# LED_board.net
KiCad netlist of a schematic drawn in EAGLE
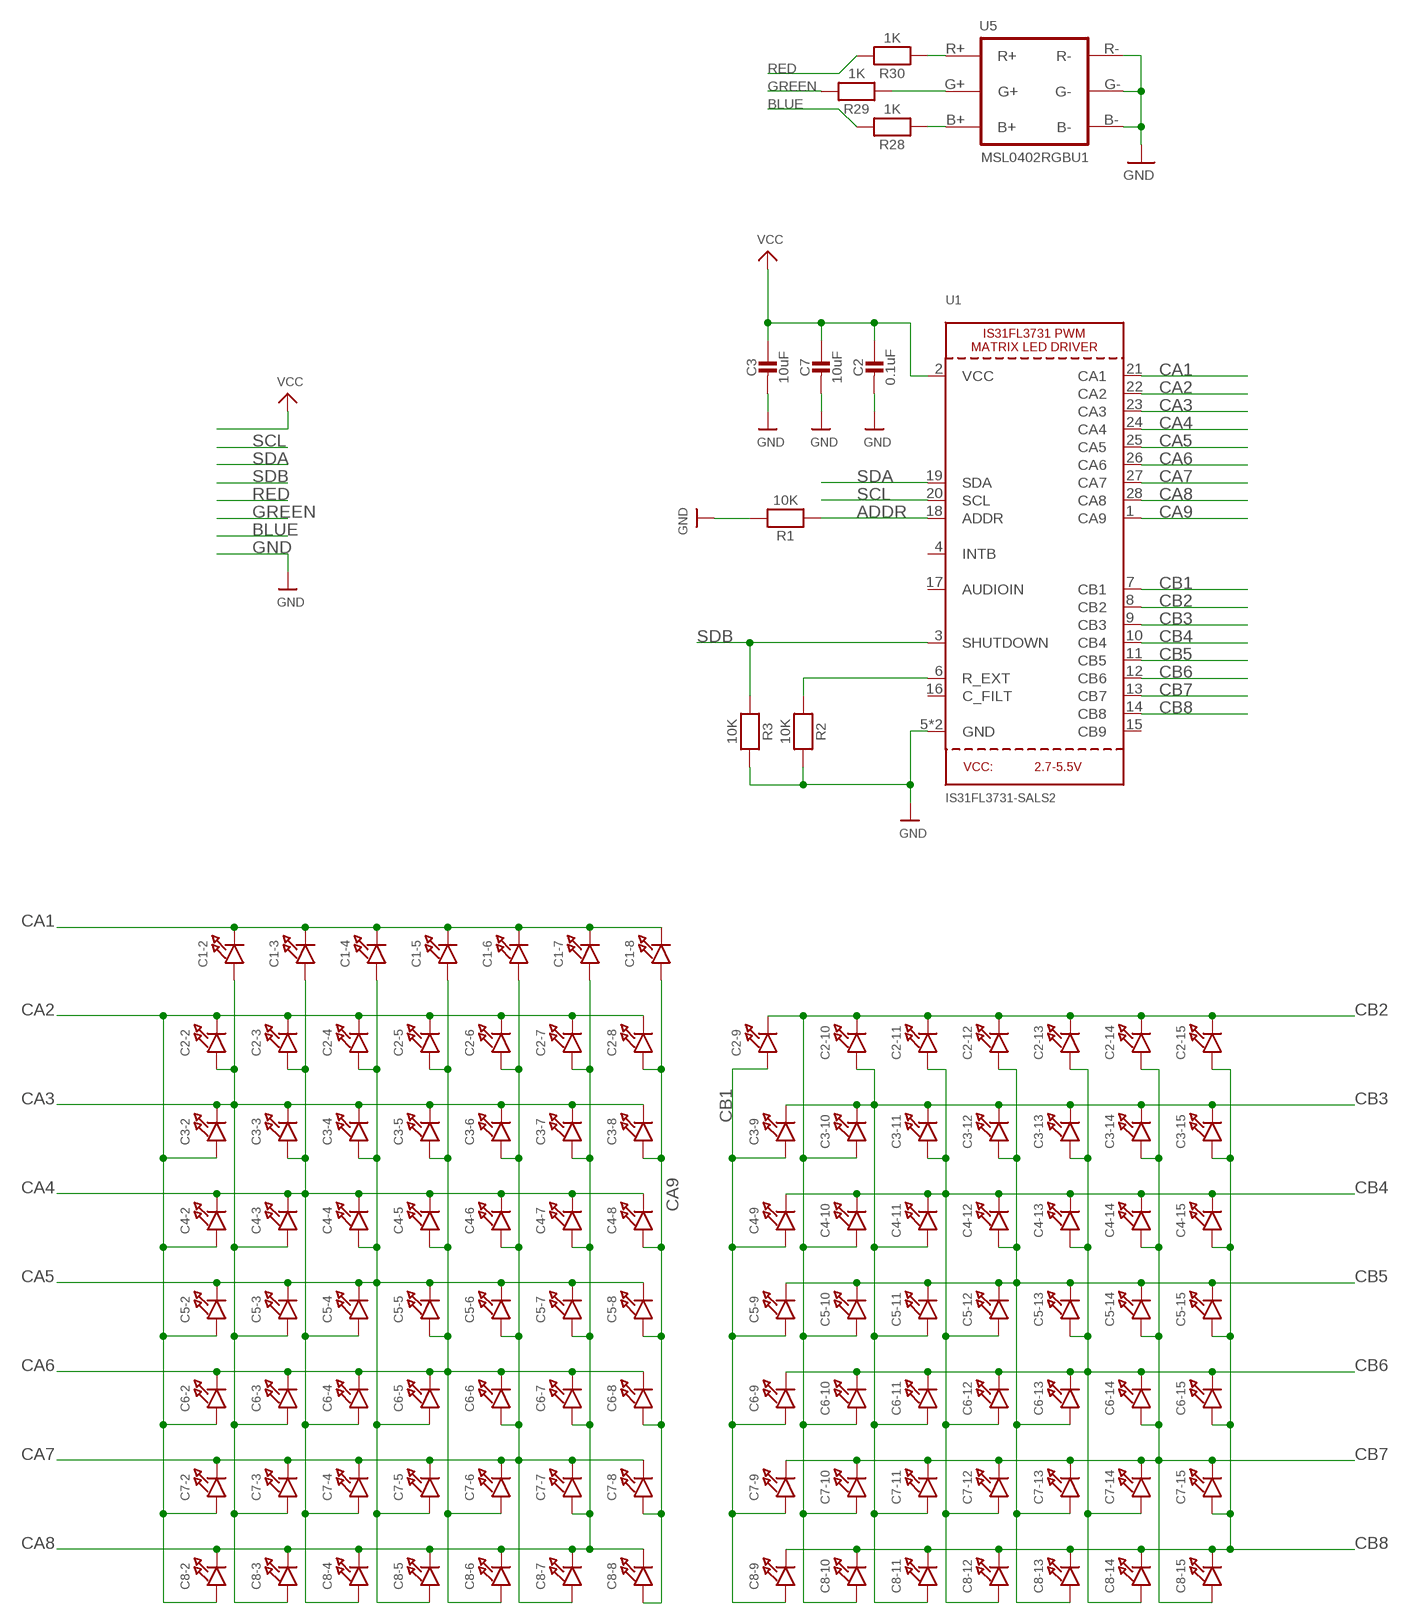
[diagram p0: schematic, sheet 1]

(export (version "E")
  (design (tool "Eeschema 10.0.6"))
  (components
    (comp (ref "C1-2")
      (value "LED0603_NOOUTLINE")
      (footprint "eagle-import:CHIPLED_0603_NOOUTLINE")
      (libsource (lib "eagle-import") (part "LED0603_NOOUTLINE"))
    )
    (comp (ref "C1-3")
      (value "LED0603_NOOUTLINE")
      (footprint "eagle-import:CHIPLED_0603_NOOUTLINE")
      (libsource (lib "eagle-import") (part "LED0603_NOOUTLINE"))
    )
    (comp (ref "C1-4")
      (value "LED0603_NOOUTLINE")
      (footprint "eagle-import:CHIPLED_0603_NOOUTLINE")
      (libsource (lib "eagle-import") (part "LED0603_NOOUTLINE"))
    )
    (comp (ref "C1-5")
      (value "LED0603_NOOUTLINE")
      (footprint "eagle-import:CHIPLED_0603_NOOUTLINE")
      (libsource (lib "eagle-import") (part "LED0603_NOOUTLINE"))
    )
    (comp (ref "C1-6")
      (value "LED0603_NOOUTLINE")
      (footprint "eagle-import:CHIPLED_0603_NOOUTLINE")
      (libsource (lib "eagle-import") (part "LED0603_NOOUTLINE"))
    )
    (comp (ref "C1-7")
      (value "LED0603_NOOUTLINE")
      (footprint "eagle-import:CHIPLED_0603_NOOUTLINE")
      (libsource (lib "eagle-import") (part "LED0603_NOOUTLINE"))
    )
    (comp (ref "C1-8")
      (value "LED0603_NOOUTLINE")
      (footprint "eagle-import:CHIPLED_0603_NOOUTLINE")
      (libsource (lib "eagle-import") (part "LED0603_NOOUTLINE"))
    )
    (comp (ref "C2")
      (value "0.1uF")
      (footprint "eagle-import:MICROBUILDER__0402MP")
      (fields (field (name "MPN") "GRM155R71C104KA88J"))
      (libsource (lib "eagle-import") (part "MICROBUILDER_CAP_CERAMIC_0402MP"))
    )
    (comp (ref "C2-2")
      (value "LED0603_NOOUTLINE")
      (footprint "eagle-import:CHIPLED_0603_NOOUTLINE")
      (libsource (lib "eagle-import") (part "LED0603_NOOUTLINE"))
    )
    (comp (ref "C2-3")
      (value "LED0603_NOOUTLINE")
      (footprint "eagle-import:CHIPLED_0603_NOOUTLINE")
      (libsource (lib "eagle-import") (part "LED0603_NOOUTLINE"))
    )
    (comp (ref "C2-4")
      (value "LED0603_NOOUTLINE")
      (footprint "eagle-import:CHIPLED_0603_NOOUTLINE")
      (libsource (lib "eagle-import") (part "LED0603_NOOUTLINE"))
    )
    (comp (ref "C2-5")
      (value "LED0603_NOOUTLINE")
      (footprint "eagle-import:CHIPLED_0603_NOOUTLINE")
      (libsource (lib "eagle-import") (part "LED0603_NOOUTLINE"))
    )
    (comp (ref "C2-6")
      (value "LED0603_NOOUTLINE")
      (footprint "eagle-import:CHIPLED_0603_NOOUTLINE")
      (libsource (lib "eagle-import") (part "LED0603_NOOUTLINE"))
    )
    (comp (ref "C2-7")
      (value "LED0603_NOOUTLINE")
      (footprint "eagle-import:CHIPLED_0603_NOOUTLINE")
      (libsource (lib "eagle-import") (part "LED0603_NOOUTLINE"))
    )
    (comp (ref "C2-8")
      (value "LED0603_NOOUTLINE")
      (footprint "eagle-import:CHIPLED_0603_NOOUTLINE")
      (libsource (lib "eagle-import") (part "LED0603_NOOUTLINE"))
    )
    (comp (ref "C2-9")
      (value "LED0603_NOOUTLINE")
      (footprint "eagle-import:CHIPLED_0603_NOOUTLINE")
      (libsource (lib "eagle-import") (part "LED0603_NOOUTLINE"))
    )
    (comp (ref "C2-10")
      (value "LED0603_NOOUTLINE")
      (footprint "eagle-import:CHIPLED_0603_NOOUTLINE")
      (libsource (lib "eagle-import") (part "LED0603_NOOUTLINE"))
    )
    (comp (ref "C2-11")
      (value "LED0603_NOOUTLINE")
      (footprint "eagle-import:CHIPLED_0603_NOOUTLINE")
      (libsource (lib "eagle-import") (part "LED0603_NOOUTLINE"))
    )
    (comp (ref "C2-12")
      (value "LED0603_NOOUTLINE")
      (footprint "eagle-import:CHIPLED_0603_NOOUTLINE")
      (libsource (lib "eagle-import") (part "LED0603_NOOUTLINE"))
    )
    (comp (ref "C2-13")
      (value "LED0603_NOOUTLINE")
      (footprint "eagle-import:CHIPLED_0603_NOOUTLINE")
      (libsource (lib "eagle-import") (part "LED0603_NOOUTLINE"))
    )
    (comp (ref "C2-14")
      (value "LED0603_NOOUTLINE")
      (footprint "eagle-import:CHIPLED_0603_NOOUTLINE")
      (libsource (lib "eagle-import") (part "LED0603_NOOUTLINE"))
    )
    (comp (ref "C2-15")
      (value "LED0603_NOOUTLINE")
      (footprint "eagle-import:CHIPLED_0603_NOOUTLINE")
      (libsource (lib "eagle-import") (part "LED0603_NOOUTLINE"))
    )
    (comp (ref "C3")
      (value "10uF")
      (footprint "eagle-import:MICROBUILDER__0402MP")
      (fields (field (name "MPN") "GRM155R71C104KA88J"))
      (libsource (lib "eagle-import") (part "MICROBUILDER_CAP_CERAMIC_0402MP"))
    )
    (comp (ref "C3-2")
      (value "LED0603_NOOUTLINE")
      (footprint "eagle-import:CHIPLED_0603_NOOUTLINE")
      (libsource (lib "eagle-import") (part "LED0603_NOOUTLINE"))
    )
    (comp (ref "C3-3")
      (value "LED0603_NOOUTLINE")
      (footprint "eagle-import:CHIPLED_0603_NOOUTLINE")
      (libsource (lib "eagle-import") (part "LED0603_NOOUTLINE"))
    )
    (comp (ref "C3-4")
      (value "LED0603_NOOUTLINE")
      (footprint "eagle-import:CHIPLED_0603_NOOUTLINE")
      (libsource (lib "eagle-import") (part "LED0603_NOOUTLINE"))
    )
    (comp (ref "C3-5")
      (value "LED0603_NOOUTLINE")
      (footprint "eagle-import:CHIPLED_0603_NOOUTLINE")
      (libsource (lib "eagle-import") (part "LED0603_NOOUTLINE"))
    )
    (comp (ref "C3-6")
      (value "LED0603_NOOUTLINE")
      (footprint "eagle-import:CHIPLED_0603_NOOUTLINE")
      (libsource (lib "eagle-import") (part "LED0603_NOOUTLINE"))
    )
    (comp (ref "C3-7")
      (value "LED0603_NOOUTLINE")
      (footprint "eagle-import:CHIPLED_0603_NOOUTLINE")
      (libsource (lib "eagle-import") (part "LED0603_NOOUTLINE"))
    )
    (comp (ref "C3-8")
      (value "LED0603_NOOUTLINE")
      (footprint "eagle-import:CHIPLED_0603_NOOUTLINE")
      (libsource (lib "eagle-import") (part "LED0603_NOOUTLINE"))
    )
    (comp (ref "C3-9")
      (value "LED0603_NOOUTLINE")
      (footprint "eagle-import:CHIPLED_0603_NOOUTLINE")
      (libsource (lib "eagle-import") (part "LED0603_NOOUTLINE"))
    )
    (comp (ref "C3-10")
      (value "LED0603_NOOUTLINE")
      (footprint "eagle-import:CHIPLED_0603_NOOUTLINE")
      (libsource (lib "eagle-import") (part "LED0603_NOOUTLINE"))
    )
    (comp (ref "C3-11")
      (value "LED0603_NOOUTLINE")
      (footprint "eagle-import:CHIPLED_0603_NOOUTLINE")
      (libsource (lib "eagle-import") (part "LED0603_NOOUTLINE"))
    )
    (comp (ref "C3-12")
      (value "LED0603_NOOUTLINE")
      (footprint "eagle-import:CHIPLED_0603_NOOUTLINE")
      (libsource (lib "eagle-import") (part "LED0603_NOOUTLINE"))
    )
    (comp (ref "C3-13")
      (value "LED0603_NOOUTLINE")
      (footprint "eagle-import:CHIPLED_0603_NOOUTLINE")
      (libsource (lib "eagle-import") (part "LED0603_NOOUTLINE"))
    )
    (comp (ref "C3-14")
      (value "LED0603_NOOUTLINE")
      (footprint "eagle-import:CHIPLED_0603_NOOUTLINE")
      (libsource (lib "eagle-import") (part "LED0603_NOOUTLINE"))
    )
    (comp (ref "C3-15")
      (value "LED0603_NOOUTLINE")
      (footprint "eagle-import:CHIPLED_0603_NOOUTLINE")
      (libsource (lib "eagle-import") (part "LED0603_NOOUTLINE"))
    )
    (comp (ref "C4-2")
      (value "LED0603_NOOUTLINE")
      (footprint "eagle-import:CHIPLED_0603_NOOUTLINE")
      (libsource (lib "eagle-import") (part "LED0603_NOOUTLINE"))
    )
    (comp (ref "C4-3")
      (value "LED0603_NOOUTLINE")
      (footprint "eagle-import:CHIPLED_0603_NOOUTLINE")
      (libsource (lib "eagle-import") (part "LED0603_NOOUTLINE"))
    )
    (comp (ref "C4-4")
      (value "LED0603_NOOUTLINE")
      (footprint "eagle-import:CHIPLED_0603_NOOUTLINE")
      (libsource (lib "eagle-import") (part "LED0603_NOOUTLINE"))
    )
    (comp (ref "C4-5")
      (value "LED0603_NOOUTLINE")
      (footprint "eagle-import:CHIPLED_0603_NOOUTLINE")
      (libsource (lib "eagle-import") (part "LED0603_NOOUTLINE"))
    )
    (comp (ref "C4-6")
      (value "LED0603_NOOUTLINE")
      (footprint "eagle-import:CHIPLED_0603_NOOUTLINE")
      (libsource (lib "eagle-import") (part "LED0603_NOOUTLINE"))
    )
    (comp (ref "C4-7")
      (value "LED0603_NOOUTLINE")
      (footprint "eagle-import:CHIPLED_0603_NOOUTLINE")
      (libsource (lib "eagle-import") (part "LED0603_NOOUTLINE"))
    )
    (comp (ref "C4-8")
      (value "LED0603_NOOUTLINE")
      (footprint "eagle-import:CHIPLED_0603_NOOUTLINE")
      (libsource (lib "eagle-import") (part "LED0603_NOOUTLINE"))
    )
    (comp (ref "C4-9")
      (value "LED0603_NOOUTLINE")
      (footprint "eagle-import:CHIPLED_0603_NOOUTLINE")
      (libsource (lib "eagle-import") (part "LED0603_NOOUTLINE"))
    )
    (comp (ref "C4-10")
      (value "LED0603_NOOUTLINE")
      (footprint "eagle-import:CHIPLED_0603_NOOUTLINE")
      (libsource (lib "eagle-import") (part "LED0603_NOOUTLINE"))
    )
    (comp (ref "C4-11")
      (value "LED0603_NOOUTLINE")
      (footprint "eagle-import:CHIPLED_0603_NOOUTLINE")
      (libsource (lib "eagle-import") (part "LED0603_NOOUTLINE"))
    )
    (comp (ref "C4-12")
      (value "LED0603_NOOUTLINE")
      (footprint "eagle-import:CHIPLED_0603_NOOUTLINE")
      (libsource (lib "eagle-import") (part "LED0603_NOOUTLINE"))
    )
    (comp (ref "C4-13")
      (value "LED0603_NOOUTLINE")
      (footprint "eagle-import:CHIPLED_0603_NOOUTLINE")
      (libsource (lib "eagle-import") (part "LED0603_NOOUTLINE"))
    )
    (comp (ref "C4-14")
      (value "LED0603_NOOUTLINE")
      (footprint "eagle-import:CHIPLED_0603_NOOUTLINE")
      (libsource (lib "eagle-import") (part "LED0603_NOOUTLINE"))
    )
    (comp (ref "C4-15")
      (value "LED0603_NOOUTLINE")
      (footprint "eagle-import:CHIPLED_0603_NOOUTLINE")
      (libsource (lib "eagle-import") (part "LED0603_NOOUTLINE"))
    )
    (comp (ref "C5-2")
      (value "LED0603_NOOUTLINE")
      (footprint "eagle-import:CHIPLED_0603_NOOUTLINE")
      (libsource (lib "eagle-import") (part "LED0603_NOOUTLINE"))
    )
    (comp (ref "C5-3")
      (value "LED0603_NOOUTLINE")
      (footprint "eagle-import:CHIPLED_0603_NOOUTLINE")
      (libsource (lib "eagle-import") (part "LED0603_NOOUTLINE"))
    )
    (comp (ref "C5-4")
      (value "LED0603_NOOUTLINE")
      (footprint "eagle-import:CHIPLED_0603_NOOUTLINE")
      (libsource (lib "eagle-import") (part "LED0603_NOOUTLINE"))
    )
    (comp (ref "C5-5")
      (value "LED0603_NOOUTLINE")
      (footprint "eagle-import:CHIPLED_0603_NOOUTLINE")
      (libsource (lib "eagle-import") (part "LED0603_NOOUTLINE"))
    )
    (comp (ref "C5-6")
      (value "LED0603_NOOUTLINE")
      (footprint "eagle-import:CHIPLED_0603_NOOUTLINE")
      (libsource (lib "eagle-import") (part "LED0603_NOOUTLINE"))
    )
    (comp (ref "C5-7")
      (value "LED0603_NOOUTLINE")
      (footprint "eagle-import:CHIPLED_0603_NOOUTLINE")
      (libsource (lib "eagle-import") (part "LED0603_NOOUTLINE"))
    )
    (comp (ref "C5-8")
      (value "LED0603_NOOUTLINE")
      (footprint "eagle-import:CHIPLED_0603_NOOUTLINE")
      (libsource (lib "eagle-import") (part "LED0603_NOOUTLINE"))
    )
    (comp (ref "C5-9")
      (value "LED0603_NOOUTLINE")
      (footprint "eagle-import:CHIPLED_0603_NOOUTLINE")
      (libsource (lib "eagle-import") (part "LED0603_NOOUTLINE"))
    )
    (comp (ref "C5-10")
      (value "LED0603_NOOUTLINE")
      (footprint "eagle-import:CHIPLED_0603_NOOUTLINE")
      (libsource (lib "eagle-import") (part "LED0603_NOOUTLINE"))
    )
    (comp (ref "C5-11")
      (value "LED0603_NOOUTLINE")
      (footprint "eagle-import:CHIPLED_0603_NOOUTLINE")
      (libsource (lib "eagle-import") (part "LED0603_NOOUTLINE"))
    )
    (comp (ref "C5-12")
      (value "LED0603_NOOUTLINE")
      (footprint "eagle-import:CHIPLED_0603_NOOUTLINE")
      (libsource (lib "eagle-import") (part "LED0603_NOOUTLINE"))
    )
    (comp (ref "C5-13")
      (value "LED0603_NOOUTLINE")
      (footprint "eagle-import:CHIPLED_0603_NOOUTLINE")
      (libsource (lib "eagle-import") (part "LED0603_NOOUTLINE"))
    )
    (comp (ref "C5-14")
      (value "LED0603_NOOUTLINE")
      (footprint "eagle-import:CHIPLED_0603_NOOUTLINE")
      (libsource (lib "eagle-import") (part "LED0603_NOOUTLINE"))
    )
    (comp (ref "C5-15")
      (value "LED0603_NOOUTLINE")
      (footprint "eagle-import:CHIPLED_0603_NOOUTLINE")
      (libsource (lib "eagle-import") (part "LED0603_NOOUTLINE"))
    )
    (comp (ref "C6-2")
      (value "LED0603_NOOUTLINE")
      (footprint "eagle-import:CHIPLED_0603_NOOUTLINE")
      (libsource (lib "eagle-import") (part "LED0603_NOOUTLINE"))
    )
    (comp (ref "C6-3")
      (value "LED0603_NOOUTLINE")
      (footprint "eagle-import:CHIPLED_0603_NOOUTLINE")
      (libsource (lib "eagle-import") (part "LED0603_NOOUTLINE"))
    )
    (comp (ref "C6-4")
      (value "LED0603_NOOUTLINE")
      (footprint "eagle-import:CHIPLED_0603_NOOUTLINE")
      (libsource (lib "eagle-import") (part "LED0603_NOOUTLINE"))
    )
    (comp (ref "C6-5")
      (value "LED0603_NOOUTLINE")
      (footprint "eagle-import:CHIPLED_0603_NOOUTLINE")
      (libsource (lib "eagle-import") (part "LED0603_NOOUTLINE"))
    )
    (comp (ref "C6-6")
      (value "LED0603_NOOUTLINE")
      (footprint "eagle-import:CHIPLED_0603_NOOUTLINE")
      (libsource (lib "eagle-import") (part "LED0603_NOOUTLINE"))
    )
    (comp (ref "C6-7")
      (value "LED0603_NOOUTLINE")
      (footprint "eagle-import:CHIPLED_0603_NOOUTLINE")
      (libsource (lib "eagle-import") (part "LED0603_NOOUTLINE"))
    )
    (comp (ref "C6-8")
      (value "LED0603_NOOUTLINE")
      (footprint "eagle-import:CHIPLED_0603_NOOUTLINE")
      (libsource (lib "eagle-import") (part "LED0603_NOOUTLINE"))
    )
    (comp (ref "C6-9")
      (value "LED0603_NOOUTLINE")
      (footprint "eagle-import:CHIPLED_0603_NOOUTLINE")
      (libsource (lib "eagle-import") (part "LED0603_NOOUTLINE"))
    )
    (comp (ref "C6-10")
      (value "LED0603_NOOUTLINE")
      (footprint "eagle-import:CHIPLED_0603_NOOUTLINE")
      (libsource (lib "eagle-import") (part "LED0603_NOOUTLINE"))
    )
    (comp (ref "C6-11")
      (value "LED0603_NOOUTLINE")
      (footprint "eagle-import:CHIPLED_0603_NOOUTLINE")
      (libsource (lib "eagle-import") (part "LED0603_NOOUTLINE"))
    )
    (comp (ref "C6-12")
      (value "LED0603_NOOUTLINE")
      (footprint "eagle-import:CHIPLED_0603_NOOUTLINE")
      (libsource (lib "eagle-import") (part "LED0603_NOOUTLINE"))
    )
    (comp (ref "C6-13")
      (value "LED0603_NOOUTLINE")
      (footprint "eagle-import:CHIPLED_0603_NOOUTLINE")
      (libsource (lib "eagle-import") (part "LED0603_NOOUTLINE"))
    )
    (comp (ref "C6-14")
      (value "LED0603_NOOUTLINE")
      (footprint "eagle-import:CHIPLED_0603_NOOUTLINE")
      (libsource (lib "eagle-import") (part "LED0603_NOOUTLINE"))
    )
    (comp (ref "C6-15")
      (value "LED0603_NOOUTLINE")
      (footprint "eagle-import:CHIPLED_0603_NOOUTLINE")
      (libsource (lib "eagle-import") (part "LED0603_NOOUTLINE"))
    )
    (comp (ref "C7")
      (value "10uF")
      (footprint "eagle-import:MICROBUILDER__0402MP")
      (fields (field (name "MPN") "GRM155R71C104KA88J"))
      (libsource (lib "eagle-import") (part "MICROBUILDER_CAP_CERAMIC_0402MP"))
    )
    (comp (ref "C7-2")
      (value "LED0603_NOOUTLINE")
      (footprint "eagle-import:CHIPLED_0603_NOOUTLINE")
      (libsource (lib "eagle-import") (part "LED0603_NOOUTLINE"))
    )
    (comp (ref "C7-3")
      (value "LED0603_NOOUTLINE")
      (footprint "eagle-import:CHIPLED_0603_NOOUTLINE")
      (libsource (lib "eagle-import") (part "LED0603_NOOUTLINE"))
    )
    (comp (ref "C7-4")
      (value "LED0603_NOOUTLINE")
      (footprint "eagle-import:CHIPLED_0603_NOOUTLINE")
      (libsource (lib "eagle-import") (part "LED0603_NOOUTLINE"))
    )
    (comp (ref "C7-5")
      (value "LED0603_NOOUTLINE")
      (footprint "eagle-import:CHIPLED_0603_NOOUTLINE")
      (libsource (lib "eagle-import") (part "LED0603_NOOUTLINE"))
    )
    (comp (ref "C7-6")
      (value "LED0603_NOOUTLINE")
      (footprint "eagle-import:CHIPLED_0603_NOOUTLINE")
      (libsource (lib "eagle-import") (part "LED0603_NOOUTLINE"))
    )
    (comp (ref "C7-7")
      (value "LED0603_NOOUTLINE")
      (footprint "eagle-import:CHIPLED_0603_NOOUTLINE")
      (libsource (lib "eagle-import") (part "LED0603_NOOUTLINE"))
    )
    (comp (ref "C7-8")
      (value "LED0603_NOOUTLINE")
      (footprint "eagle-import:CHIPLED_0603_NOOUTLINE")
      (libsource (lib "eagle-import") (part "LED0603_NOOUTLINE"))
    )
    (comp (ref "C7-9")
      (value "LED0603_NOOUTLINE")
      (footprint "eagle-import:CHIPLED_0603_NOOUTLINE")
      (libsource (lib "eagle-import") (part "LED0603_NOOUTLINE"))
    )
    (comp (ref "C7-10")
      (value "LED0603_NOOUTLINE")
      (footprint "eagle-import:CHIPLED_0603_NOOUTLINE")
      (libsource (lib "eagle-import") (part "LED0603_NOOUTLINE"))
    )
    (comp (ref "C7-11")
      (value "LED0603_NOOUTLINE")
      (footprint "eagle-import:CHIPLED_0603_NOOUTLINE")
      (libsource (lib "eagle-import") (part "LED0603_NOOUTLINE"))
    )
    (comp (ref "C7-12")
      (value "LED0603_NOOUTLINE")
      (footprint "eagle-import:CHIPLED_0603_NOOUTLINE")
      (libsource (lib "eagle-import") (part "LED0603_NOOUTLINE"))
    )
    (comp (ref "C7-13")
      (value "LED0603_NOOUTLINE")
      (footprint "eagle-import:CHIPLED_0603_NOOUTLINE")
      (libsource (lib "eagle-import") (part "LED0603_NOOUTLINE"))
    )
    (comp (ref "C7-14")
      (value "LED0603_NOOUTLINE")
      (footprint "eagle-import:CHIPLED_0603_NOOUTLINE")
      (libsource (lib "eagle-import") (part "LED0603_NOOUTLINE"))
    )
    (comp (ref "C7-15")
      (value "LED0603_NOOUTLINE")
      (footprint "eagle-import:CHIPLED_0603_NOOUTLINE")
      (libsource (lib "eagle-import") (part "LED0603_NOOUTLINE"))
    )
    (comp (ref "C8-2")
      (value "LED0603_NOOUTLINE")
      (footprint "eagle-import:CHIPLED_0603_NOOUTLINE")
      (libsource (lib "eagle-import") (part "LED0603_NOOUTLINE"))
    )
    (comp (ref "C8-3")
      (value "LED0603_NOOUTLINE")
      (footprint "eagle-import:CHIPLED_0603_NOOUTLINE")
      (libsource (lib "eagle-import") (part "LED0603_NOOUTLINE"))
    )
    (comp (ref "C8-4")
      (value "LED0603_NOOUTLINE")
      (footprint "eagle-import:CHIPLED_0603_NOOUTLINE")
      (libsource (lib "eagle-import") (part "LED0603_NOOUTLINE"))
    )
    (comp (ref "C8-5")
      (value "LED0603_NOOUTLINE")
      (footprint "eagle-import:CHIPLED_0603_NOOUTLINE")
      (libsource (lib "eagle-import") (part "LED0603_NOOUTLINE"))
    )
    (comp (ref "C8-6")
      (value "LED0603_NOOUTLINE")
      (footprint "eagle-import:CHIPLED_0603_NOOUTLINE")
      (libsource (lib "eagle-import") (part "LED0603_NOOUTLINE"))
    )
    (comp (ref "C8-7")
      (value "LED0603_NOOUTLINE")
      (footprint "eagle-import:CHIPLED_0603_NOOUTLINE")
      (libsource (lib "eagle-import") (part "LED0603_NOOUTLINE"))
    )
    (comp (ref "C8-8")
      (value "LED0603_NOOUTLINE")
      (footprint "eagle-import:CHIPLED_0603_NOOUTLINE")
      (libsource (lib "eagle-import") (part "LED0603_NOOUTLINE"))
    )
    (comp (ref "C8-9")
      (value "LED0603_NOOUTLINE")
      (footprint "eagle-import:CHIPLED_0603_NOOUTLINE")
      (libsource (lib "eagle-import") (part "LED0603_NOOUTLINE"))
    )
    (comp (ref "C8-10")
      (value "LED0603_NOOUTLINE")
      (footprint "eagle-import:CHIPLED_0603_NOOUTLINE")
      (libsource (lib "eagle-import") (part "LED0603_NOOUTLINE"))
    )
    (comp (ref "C8-11")
      (value "LED0603_NOOUTLINE")
      (footprint "eagle-import:CHIPLED_0603_NOOUTLINE")
      (libsource (lib "eagle-import") (part "LED0603_NOOUTLINE"))
    )
    (comp (ref "C8-12")
      (value "LED0603_NOOUTLINE")
      (footprint "eagle-import:CHIPLED_0603_NOOUTLINE")
      (libsource (lib "eagle-import") (part "LED0603_NOOUTLINE"))
    )
    (comp (ref "C8-13")
      (value "LED0603_NOOUTLINE")
      (footprint "eagle-import:CHIPLED_0603_NOOUTLINE")
      (libsource (lib "eagle-import") (part "LED0603_NOOUTLINE"))
    )
    (comp (ref "C8-14")
      (value "LED0603_NOOUTLINE")
      (footprint "eagle-import:CHIPLED_0603_NOOUTLINE")
      (libsource (lib "eagle-import") (part "LED0603_NOOUTLINE"))
    )
    (comp (ref "C8-15")
      (value "LED0603_NOOUTLINE")
      (footprint "eagle-import:CHIPLED_0603_NOOUTLINE")
      (libsource (lib "eagle-import") (part "LED0603_NOOUTLINE"))
    )
    (comp (ref "R1")
      (value "10K")
      (footprint "eagle-import:MICROBUILDER__0402MP")
      (fields (field (name "MPN") "RC0402FR-7W10KL"))
      (libsource (lib "eagle-import") (part "MICROBUILDER_RESISTOR_0402MP"))
    )
    (comp (ref "R2")
      (value "10K")
      (footprint "eagle-import:MICROBUILDER__0402MP")
      (fields (field (name "MPN") "RC0402FR-7W10KL"))
      (libsource (lib "eagle-import") (part "MICROBUILDER_RESISTOR_0402MP"))
    )
    (comp (ref "R3")
      (value "10K")
      (footprint "eagle-import:MICROBUILDER__0402MP")
      (fields (field (name "MPN") "RC0402FR-7W10KL"))
      (libsource (lib "eagle-import") (part "MICROBUILDER_RESISTOR_0402MP"))
    )
    (comp (ref "R28")
      (value "1K")
      (footprint "eagle-import:MICROBUILDER__0402MP")
      (fields (field (name "MPN") "RC0402FR-7W10KL"))
      (libsource (lib "eagle-import") (part "MICROBUILDER_RESISTOR_0402MP"))
    )
    (comp (ref "R29")
      (value "1K")
      (footprint "eagle-import:MICROBUILDER__0402MP")
      (fields (field (name "MPN") "RC0402FR-7W10KL"))
      (libsource (lib "eagle-import") (part "MICROBUILDER_RESISTOR_0402MP"))
    )
    (comp (ref "R30")
      (value "1K")
      (footprint "eagle-import:MICROBUILDER__0402MP")
      (fields (field (name "MPN") "RC0402FR-7W10KL"))
      (libsource (lib "eagle-import") (part "MICROBUILDER_RESISTOR_0402MP"))
    )
    (comp (ref "U1")
      (value "IS31FL3731-SALS2")
      (footprint "eagle-import:QFN28_4MM_0.4MM")
      (libsource (lib "eagle-import") (part "IS31FL3731QFN"))
    )
    (comp (ref "U5")
      (value "MSL0402RGBU1")
      (footprint "eagle-import:SMD-6")
      (libsource (lib "eagle-import") (part "MSL0402RGBU1"))
    )
  )
  (nets
    (net (code "1") (name "/ADDR") (class "Default")
      (node (ref "R1") (pin "1") (pinfunction "1_1") (pintype "passive"))
      (node (ref "U1") (pin "18") (pinfunction "ADDR_18") (pintype "bidirectional"))
    )
    (net (code "2") (name "/BLUE") (class "Default")
      (node (ref "R28") (pin "2") (pinfunction "2_2") (pintype "passive"))
    )
    (net (code "3") (name "/CA1") (class "Default")
      (node (ref "C1-2") (pin "C") (pinfunction "C_C") (pintype "passive"))
      (node (ref "C1-3") (pin "C") (pinfunction "C_C") (pintype "passive"))
      (node (ref "C1-4") (pin "C") (pinfunction "C_C") (pintype "passive"))
      (node (ref "C1-5") (pin "C") (pinfunction "C_C") (pintype "passive"))
      (node (ref "C1-6") (pin "C") (pinfunction "C_C") (pintype "passive"))
      (node (ref "C1-7") (pin "C") (pinfunction "C_C") (pintype "passive"))
      (node (ref "C1-8") (pin "C") (pinfunction "C_C") (pintype "passive"))
      (node (ref "U1") (pin "21") (pinfunction "CA1_21") (pintype "bidirectional"))
    )
    (net (code "4") (name "/CA2") (class "Default")
      (node (ref "C2-2") (pin "C") (pinfunction "C_C") (pintype "passive"))
      (node (ref "C2-3") (pin "C") (pinfunction "C_C") (pintype "passive"))
      (node (ref "C2-4") (pin "C") (pinfunction "C_C") (pintype "passive"))
      (node (ref "C2-5") (pin "C") (pinfunction "C_C") (pintype "passive"))
      (node (ref "C2-6") (pin "C") (pinfunction "C_C") (pintype "passive"))
      (node (ref "C2-7") (pin "C") (pinfunction "C_C") (pintype "passive"))
      (node (ref "C2-8") (pin "C") (pinfunction "C_C") (pintype "passive"))
      (node (ref "C3-2") (pin "A") (pinfunction "A_A") (pintype "passive"))
      (node (ref "C4-2") (pin "A") (pinfunction "A_A") (pintype "passive"))
      (node (ref "C5-2") (pin "A") (pinfunction "A_A") (pintype "passive"))
      (node (ref "C6-2") (pin "A") (pinfunction "A_A") (pintype "passive"))
      (node (ref "C7-2") (pin "A") (pinfunction "A_A") (pintype "passive"))
      (node (ref "C8-2") (pin "A") (pinfunction "A_A") (pintype "passive"))
      (node (ref "U1") (pin "22") (pinfunction "CA2_22") (pintype "bidirectional"))
    )
    (net (code "5") (name "/CA3") (class "Default")
      (node (ref "C1-2") (pin "A") (pinfunction "A_A") (pintype "passive"))
      (node (ref "C2-2") (pin "A") (pinfunction "A_A") (pintype "passive"))
      (node (ref "C3-2") (pin "C") (pinfunction "C_C") (pintype "passive"))
      (node (ref "C3-3") (pin "C") (pinfunction "C_C") (pintype "passive"))
      (node (ref "C3-4") (pin "C") (pinfunction "C_C") (pintype "passive"))
      (node (ref "C3-5") (pin "C") (pinfunction "C_C") (pintype "passive"))
      (node (ref "C3-6") (pin "C") (pinfunction "C_C") (pintype "passive"))
      (node (ref "C3-7") (pin "C") (pinfunction "C_C") (pintype "passive"))
      (node (ref "C3-8") (pin "C") (pinfunction "C_C") (pintype "passive"))
      (node (ref "C4-3") (pin "A") (pinfunction "A_A") (pintype "passive"))
      (node (ref "C5-3") (pin "A") (pinfunction "A_A") (pintype "passive"))
      (node (ref "C6-3") (pin "A") (pinfunction "A_A") (pintype "passive"))
      (node (ref "C7-3") (pin "A") (pinfunction "A_A") (pintype "passive"))
      (node (ref "C8-3") (pin "A") (pinfunction "A_A") (pintype "passive"))
      (node (ref "U1") (pin "23") (pinfunction "CA3_23") (pintype "bidirectional"))
    )
    (net (code "6") (name "/CA4") (class "Default")
      (node (ref "C1-3") (pin "A") (pinfunction "A_A") (pintype "passive"))
      (node (ref "C2-3") (pin "A") (pinfunction "A_A") (pintype "passive"))
      (node (ref "C3-3") (pin "A") (pinfunction "A_A") (pintype "passive"))
      (node (ref "C4-2") (pin "C") (pinfunction "C_C") (pintype "passive"))
      (node (ref "C4-3") (pin "C") (pinfunction "C_C") (pintype "passive"))
      (node (ref "C4-4") (pin "C") (pinfunction "C_C") (pintype "passive"))
      (node (ref "C4-5") (pin "C") (pinfunction "C_C") (pintype "passive"))
      (node (ref "C4-6") (pin "C") (pinfunction "C_C") (pintype "passive"))
      (node (ref "C4-7") (pin "C") (pinfunction "C_C") (pintype "passive"))
      (node (ref "C4-8") (pin "C") (pinfunction "C_C") (pintype "passive"))
      (node (ref "C5-4") (pin "A") (pinfunction "A_A") (pintype "passive"))
      (node (ref "C6-4") (pin "A") (pinfunction "A_A") (pintype "passive"))
      (node (ref "C7-4") (pin "A") (pinfunction "A_A") (pintype "passive"))
      (node (ref "C8-4") (pin "A") (pinfunction "A_A") (pintype "passive"))
      (node (ref "U1") (pin "24") (pinfunction "CA4_24") (pintype "bidirectional"))
    )
    (net (code "7") (name "/CA5") (class "Default")
      (node (ref "C1-4") (pin "A") (pinfunction "A_A") (pintype "passive"))
      (node (ref "C2-4") (pin "A") (pinfunction "A_A") (pintype "passive"))
      (node (ref "C3-4") (pin "A") (pinfunction "A_A") (pintype "passive"))
      (node (ref "C4-4") (pin "A") (pinfunction "A_A") (pintype "passive"))
      (node (ref "C5-2") (pin "C") (pinfunction "C_C") (pintype "passive"))
      (node (ref "C5-3") (pin "C") (pinfunction "C_C") (pintype "passive"))
      (node (ref "C5-4") (pin "C") (pinfunction "C_C") (pintype "passive"))
      (node (ref "C5-5") (pin "C") (pinfunction "C_C") (pintype "passive"))
      (node (ref "C5-6") (pin "C") (pinfunction "C_C") (pintype "passive"))
      (node (ref "C5-7") (pin "C") (pinfunction "C_C") (pintype "passive"))
      (node (ref "C5-8") (pin "C") (pinfunction "C_C") (pintype "passive"))
      (node (ref "C6-5") (pin "A") (pinfunction "A_A") (pintype "passive"))
      (node (ref "C7-5") (pin "A") (pinfunction "A_A") (pintype "passive"))
      (node (ref "C8-5") (pin "A") (pinfunction "A_A") (pintype "passive"))
      (node (ref "U1") (pin "25") (pinfunction "CA5_25") (pintype "bidirectional"))
    )
    (net (code "8") (name "/CA6") (class "Default")
      (node (ref "C1-5") (pin "A") (pinfunction "A_A") (pintype "passive"))
      (node (ref "C2-5") (pin "A") (pinfunction "A_A") (pintype "passive"))
      (node (ref "C3-5") (pin "A") (pinfunction "A_A") (pintype "passive"))
      (node (ref "C4-5") (pin "A") (pinfunction "A_A") (pintype "passive"))
      (node (ref "C5-5") (pin "A") (pinfunction "A_A") (pintype "passive"))
      (node (ref "C6-2") (pin "C") (pinfunction "C_C") (pintype "passive"))
      (node (ref "C6-3") (pin "C") (pinfunction "C_C") (pintype "passive"))
      (node (ref "C6-4") (pin "C") (pinfunction "C_C") (pintype "passive"))
      (node (ref "C6-5") (pin "C") (pinfunction "C_C") (pintype "passive"))
      (node (ref "C6-6") (pin "C") (pinfunction "C_C") (pintype "passive"))
      (node (ref "C6-7") (pin "C") (pinfunction "C_C") (pintype "passive"))
      (node (ref "C6-8") (pin "C") (pinfunction "C_C") (pintype "passive"))
      (node (ref "C7-6") (pin "A") (pinfunction "A_A") (pintype "passive"))
      (node (ref "C8-6") (pin "A") (pinfunction "A_A") (pintype "passive"))
      (node (ref "U1") (pin "26") (pinfunction "CA6_26") (pintype "bidirectional"))
    )
    (net (code "9") (name "/CA7") (class "Default")
      (node (ref "C1-6") (pin "A") (pinfunction "A_A") (pintype "passive"))
      (node (ref "C2-6") (pin "A") (pinfunction "A_A") (pintype "passive"))
      (node (ref "C3-6") (pin "A") (pinfunction "A_A") (pintype "passive"))
      (node (ref "C4-6") (pin "A") (pinfunction "A_A") (pintype "passive"))
      (node (ref "C5-6") (pin "A") (pinfunction "A_A") (pintype "passive"))
      (node (ref "C6-6") (pin "A") (pinfunction "A_A") (pintype "passive"))
      (node (ref "C7-2") (pin "C") (pinfunction "C_C") (pintype "passive"))
      (node (ref "C7-3") (pin "C") (pinfunction "C_C") (pintype "passive"))
      (node (ref "C7-4") (pin "C") (pinfunction "C_C") (pintype "passive"))
      (node (ref "C7-5") (pin "C") (pinfunction "C_C") (pintype "passive"))
      (node (ref "C7-6") (pin "C") (pinfunction "C_C") (pintype "passive"))
      (node (ref "C7-7") (pin "C") (pinfunction "C_C") (pintype "passive"))
      (node (ref "C7-8") (pin "C") (pinfunction "C_C") (pintype "passive"))
      (node (ref "C8-7") (pin "A") (pinfunction "A_A") (pintype "passive"))
      (node (ref "U1") (pin "27") (pinfunction "CA7_27") (pintype "bidirectional"))
    )
    (net (code "10") (name "/CA8") (class "Default")
      (node (ref "C1-7") (pin "A") (pinfunction "A_A") (pintype "passive"))
      (node (ref "C2-7") (pin "A") (pinfunction "A_A") (pintype "passive"))
      (node (ref "C3-7") (pin "A") (pinfunction "A_A") (pintype "passive"))
      (node (ref "C4-7") (pin "A") (pinfunction "A_A") (pintype "passive"))
      (node (ref "C5-7") (pin "A") (pinfunction "A_A") (pintype "passive"))
      (node (ref "C6-7") (pin "A") (pinfunction "A_A") (pintype "passive"))
      (node (ref "C7-7") (pin "A") (pinfunction "A_A") (pintype "passive"))
      (node (ref "C8-2") (pin "C") (pinfunction "C_C") (pintype "passive"))
      (node (ref "C8-3") (pin "C") (pinfunction "C_C") (pintype "passive"))
      (node (ref "C8-4") (pin "C") (pinfunction "C_C") (pintype "passive"))
      (node (ref "C8-5") (pin "C") (pinfunction "C_C") (pintype "passive"))
      (node (ref "C8-6") (pin "C") (pinfunction "C_C") (pintype "passive"))
      (node (ref "C8-7") (pin "C") (pinfunction "C_C") (pintype "passive"))
      (node (ref "C8-8") (pin "C") (pinfunction "C_C") (pintype "passive"))
      (node (ref "U1") (pin "28") (pinfunction "CA8_28") (pintype "bidirectional"))
    )
    (net (code "11") (name "/CA9") (class "Default")
      (node (ref "C1-8") (pin "A") (pinfunction "A_A") (pintype "passive"))
      (node (ref "C2-8") (pin "A") (pinfunction "A_A") (pintype "passive"))
      (node (ref "C3-8") (pin "A") (pinfunction "A_A") (pintype "passive"))
      (node (ref "C4-8") (pin "A") (pinfunction "A_A") (pintype "passive"))
      (node (ref "C5-8") (pin "A") (pinfunction "A_A") (pintype "passive"))
      (node (ref "C6-8") (pin "A") (pinfunction "A_A") (pintype "passive"))
      (node (ref "C7-8") (pin "A") (pinfunction "A_A") (pintype "passive"))
      (node (ref "C8-8") (pin "A") (pinfunction "A_A") (pintype "passive"))
      (node (ref "U1") (pin "1") (pinfunction "CA9_1") (pintype "bidirectional"))
    )
    (net (code "12") (name "/CB1") (class "Default")
      (node (ref "C2-9") (pin "A") (pinfunction "A_A") (pintype "passive"))
      (node (ref "C3-9") (pin "A") (pinfunction "A_A") (pintype "passive"))
      (node (ref "C4-9") (pin "A") (pinfunction "A_A") (pintype "passive"))
      (node (ref "C5-9") (pin "A") (pinfunction "A_A") (pintype "passive"))
      (node (ref "C6-9") (pin "A") (pinfunction "A_A") (pintype "passive"))
      (node (ref "C7-9") (pin "A") (pinfunction "A_A") (pintype "passive"))
      (node (ref "C8-9") (pin "A") (pinfunction "A_A") (pintype "passive"))
      (node (ref "U1") (pin "7") (pinfunction "CB1_7") (pintype "bidirectional"))
    )
    (net (code "13") (name "/CB2") (class "Default")
      (node (ref "C2-10") (pin "C") (pinfunction "C_C") (pintype "passive"))
      (node (ref "C2-11") (pin "C") (pinfunction "C_C") (pintype "passive"))
      (node (ref "C2-12") (pin "C") (pinfunction "C_C") (pintype "passive"))
      (node (ref "C2-13") (pin "C") (pinfunction "C_C") (pintype "passive"))
      (node (ref "C2-14") (pin "C") (pinfunction "C_C") (pintype "passive"))
      (node (ref "C2-15") (pin "C") (pinfunction "C_C") (pintype "passive"))
      (node (ref "C2-9") (pin "C") (pinfunction "C_C") (pintype "passive"))
      (node (ref "C3-10") (pin "A") (pinfunction "A_A") (pintype "passive"))
      (node (ref "C4-10") (pin "A") (pinfunction "A_A") (pintype "passive"))
      (node (ref "C5-10") (pin "A") (pinfunction "A_A") (pintype "passive"))
      (node (ref "C6-10") (pin "A") (pinfunction "A_A") (pintype "passive"))
      (node (ref "C7-10") (pin "A") (pinfunction "A_A") (pintype "passive"))
      (node (ref "C8-10") (pin "A") (pinfunction "A_A") (pintype "passive"))
      (node (ref "U1") (pin "8") (pinfunction "CB2_8") (pintype "bidirectional"))
    )
    (net (code "14") (name "/CB3") (class "Default")
      (node (ref "C2-10") (pin "A") (pinfunction "A_A") (pintype "passive"))
      (node (ref "C3-10") (pin "C") (pinfunction "C_C") (pintype "passive"))
      (node (ref "C3-11") (pin "C") (pinfunction "C_C") (pintype "passive"))
      (node (ref "C3-12") (pin "C") (pinfunction "C_C") (pintype "passive"))
      (node (ref "C3-13") (pin "C") (pinfunction "C_C") (pintype "passive"))
      (node (ref "C3-14") (pin "C") (pinfunction "C_C") (pintype "passive"))
      (node (ref "C3-15") (pin "C") (pinfunction "C_C") (pintype "passive"))
      (node (ref "C3-9") (pin "C") (pinfunction "C_C") (pintype "passive"))
      (node (ref "C4-11") (pin "A") (pinfunction "A_A") (pintype "passive"))
      (node (ref "C5-11") (pin "A") (pinfunction "A_A") (pintype "passive"))
      (node (ref "C6-11") (pin "A") (pinfunction "A_A") (pintype "passive"))
      (node (ref "C7-11") (pin "A") (pinfunction "A_A") (pintype "passive"))
      (node (ref "C8-11") (pin "A") (pinfunction "A_A") (pintype "passive"))
      (node (ref "U1") (pin "9") (pinfunction "CB3_9") (pintype "bidirectional"))
    )
    (net (code "15") (name "/CB4") (class "Default")
      (node (ref "C2-11") (pin "A") (pinfunction "A_A") (pintype "passive"))
      (node (ref "C3-11") (pin "A") (pinfunction "A_A") (pintype "passive"))
      (node (ref "C4-10") (pin "C") (pinfunction "C_C") (pintype "passive"))
      (node (ref "C4-11") (pin "C") (pinfunction "C_C") (pintype "passive"))
      (node (ref "C4-12") (pin "C") (pinfunction "C_C") (pintype "passive"))
      (node (ref "C4-13") (pin "C") (pinfunction "C_C") (pintype "passive"))
      (node (ref "C4-14") (pin "C") (pinfunction "C_C") (pintype "passive"))
      (node (ref "C4-15") (pin "C") (pinfunction "C_C") (pintype "passive"))
      (node (ref "C4-9") (pin "C") (pinfunction "C_C") (pintype "passive"))
      (node (ref "C5-12") (pin "A") (pinfunction "A_A") (pintype "passive"))
      (node (ref "C6-12") (pin "A") (pinfunction "A_A") (pintype "passive"))
      (node (ref "C7-12") (pin "A") (pinfunction "A_A") (pintype "passive"))
      (node (ref "C8-12") (pin "A") (pinfunction "A_A") (pintype "passive"))
      (node (ref "U1") (pin "10") (pinfunction "CB4_10") (pintype "bidirectional"))
    )
    (net (code "16") (name "/CB5") (class "Default")
      (node (ref "C2-12") (pin "A") (pinfunction "A_A") (pintype "passive"))
      (node (ref "C3-12") (pin "A") (pinfunction "A_A") (pintype "passive"))
      (node (ref "C4-12") (pin "A") (pinfunction "A_A") (pintype "passive"))
      (node (ref "C5-10") (pin "C") (pinfunction "C_C") (pintype "passive"))
      (node (ref "C5-11") (pin "C") (pinfunction "C_C") (pintype "passive"))
      (node (ref "C5-12") (pin "C") (pinfunction "C_C") (pintype "passive"))
      (node (ref "C5-13") (pin "C") (pinfunction "C_C") (pintype "passive"))
      (node (ref "C5-14") (pin "C") (pinfunction "C_C") (pintype "passive"))
      (node (ref "C5-15") (pin "C") (pinfunction "C_C") (pintype "passive"))
      (node (ref "C5-9") (pin "C") (pinfunction "C_C") (pintype "passive"))
      (node (ref "C6-13") (pin "A") (pinfunction "A_A") (pintype "passive"))
      (node (ref "C7-13") (pin "A") (pinfunction "A_A") (pintype "passive"))
      (node (ref "C8-13") (pin "A") (pinfunction "A_A") (pintype "passive"))
      (node (ref "U1") (pin "11") (pinfunction "CB5_11") (pintype "bidirectional"))
    )
    (net (code "17") (name "/CB6") (class "Default")
      (node (ref "C2-13") (pin "A") (pinfunction "A_A") (pintype "passive"))
      (node (ref "C3-13") (pin "A") (pinfunction "A_A") (pintype "passive"))
      (node (ref "C4-13") (pin "A") (pinfunction "A_A") (pintype "passive"))
      (node (ref "C5-13") (pin "A") (pinfunction "A_A") (pintype "passive"))
      (node (ref "C6-10") (pin "C") (pinfunction "C_C") (pintype "passive"))
      (node (ref "C6-11") (pin "C") (pinfunction "C_C") (pintype "passive"))
      (node (ref "C6-12") (pin "C") (pinfunction "C_C") (pintype "passive"))
      (node (ref "C6-13") (pin "C") (pinfunction "C_C") (pintype "passive"))
      (node (ref "C6-14") (pin "C") (pinfunction "C_C") (pintype "passive"))
      (node (ref "C6-15") (pin "C") (pinfunction "C_C") (pintype "passive"))
      (node (ref "C6-9") (pin "C") (pinfunction "C_C") (pintype "passive"))
      (node (ref "C7-14") (pin "A") (pinfunction "A_A") (pintype "passive"))
      (node (ref "C8-14") (pin "A") (pinfunction "A_A") (pintype "passive"))
      (node (ref "U1") (pin "12") (pinfunction "CB6_12") (pintype "bidirectional"))
    )
    (net (code "18") (name "/CB7") (class "Default")
      (node (ref "C2-14") (pin "A") (pinfunction "A_A") (pintype "passive"))
      (node (ref "C3-14") (pin "A") (pinfunction "A_A") (pintype "passive"))
      (node (ref "C4-14") (pin "A") (pinfunction "A_A") (pintype "passive"))
      (node (ref "C5-14") (pin "A") (pinfunction "A_A") (pintype "passive"))
      (node (ref "C6-14") (pin "A") (pinfunction "A_A") (pintype "passive"))
      (node (ref "C7-10") (pin "C") (pinfunction "C_C") (pintype "passive"))
      (node (ref "C7-11") (pin "C") (pinfunction "C_C") (pintype "passive"))
      (node (ref "C7-12") (pin "C") (pinfunction "C_C") (pintype "passive"))
      (node (ref "C7-13") (pin "C") (pinfunction "C_C") (pintype "passive"))
      (node (ref "C7-14") (pin "C") (pinfunction "C_C") (pintype "passive"))
      (node (ref "C7-15") (pin "C") (pinfunction "C_C") (pintype "passive"))
      (node (ref "C7-9") (pin "C") (pinfunction "C_C") (pintype "passive"))
      (node (ref "C8-15") (pin "A") (pinfunction "A_A") (pintype "passive"))
      (node (ref "U1") (pin "13") (pinfunction "CB7_13") (pintype "bidirectional"))
    )
    (net (code "19") (name "/CB8") (class "Default")
      (node (ref "C2-15") (pin "A") (pinfunction "A_A") (pintype "passive"))
      (node (ref "C3-15") (pin "A") (pinfunction "A_A") (pintype "passive"))
      (node (ref "C4-15") (pin "A") (pinfunction "A_A") (pintype "passive"))
      (node (ref "C5-15") (pin "A") (pinfunction "A_A") (pintype "passive"))
      (node (ref "C6-15") (pin "A") (pinfunction "A_A") (pintype "passive"))
      (node (ref "C7-15") (pin "A") (pinfunction "A_A") (pintype "passive"))
      (node (ref "C8-10") (pin "C") (pinfunction "C_C") (pintype "passive"))
      (node (ref "C8-11") (pin "C") (pinfunction "C_C") (pintype "passive"))
      (node (ref "C8-12") (pin "C") (pinfunction "C_C") (pintype "passive"))
      (node (ref "C8-13") (pin "C") (pinfunction "C_C") (pintype "passive"))
      (node (ref "C8-14") (pin "C") (pinfunction "C_C") (pintype "passive"))
      (node (ref "C8-15") (pin "C") (pinfunction "C_C") (pintype "passive"))
      (node (ref "C8-9") (pin "C") (pinfunction "C_C") (pintype "passive"))
      (node (ref "U1") (pin "14") (pinfunction "CB8_14") (pintype "bidirectional"))
    )
    (net (code "20") (name "/GREEN") (class "Default")
      (node (ref "R29") (pin "2") (pinfunction "2_2") (pintype "passive"))
    )
    (net (code "21") (name "/RED") (class "Default")
      (node (ref "R30") (pin "2") (pinfunction "2_2") (pintype "passive"))
    )
    (net (code "22") (name "/SCL") (class "Default")
      (node (ref "U1") (pin "20") (pinfunction "SCL_20") (pintype "bidirectional"))
    )
    (net (code "23") (name "/SDA") (class "Default")
      (node (ref "U1") (pin "19") (pinfunction "SDA_19") (pintype "bidirectional"))
    )
    (net (code "24") (name "/SDB") (class "Default")
      (node (ref "R3") (pin "1") (pinfunction "1_1") (pintype "passive"))
      (node (ref "U1") (pin "3") (pinfunction "SHUTDOWN_3") (pintype "input"))
    )
    (net (code "25") (name "GND") (class "Default")
      (node (ref "C2") (pin "2") (pinfunction "2_2") (pintype "passive"))
      (node (ref "C3") (pin "2") (pinfunction "2_2") (pintype "passive"))
      (node (ref "C7") (pin "2") (pinfunction "2_2") (pintype "passive"))
      (node (ref "R1") (pin "2") (pinfunction "2_2") (pintype "passive"))
      (node (ref "R2") (pin "2") (pinfunction "2_2") (pintype "passive"))
      (node (ref "R3") (pin "2") (pinfunction "2_2") (pintype "passive"))
      (node (ref "U1") (pin "5") (pinfunction "GND_5") (pintype "power_in"))
      (node (ref "U1") (pin "THERMAL") (pinfunction "GND_THERMAL") (pintype "power_in"))
      (node (ref "U5") (pin "B-") (pinfunction "B-_B-") (pintype "bidirectional"))
      (node (ref "U5") (pin "G-") (pinfunction "G-_G-") (pintype "bidirectional"))
      (node (ref "U5") (pin "R-") (pinfunction "R-_R-") (pintype "bidirectional"))
    )
    (net (code "26") (name "Net-(R28-Pad1)") (class "Default")
      (node (ref "R28") (pin "1") (pinfunction "1_1") (pintype "passive"))
      (node (ref "U5") (pin "B+") (pinfunction "B+_B+") (pintype "bidirectional"))
    )
    (net (code "27") (name "Net-(R29-Pad1)") (class "Default")
      (node (ref "R29") (pin "1") (pinfunction "1_1") (pintype "passive"))
      (node (ref "U5") (pin "G+") (pinfunction "G+_G+") (pintype "bidirectional"))
    )
    (net (code "28") (name "Net-(R30-Pad1)") (class "Default")
      (node (ref "R30") (pin "1") (pinfunction "1_1") (pintype "passive"))
      (node (ref "U5") (pin "R+") (pinfunction "R+_R+") (pintype "bidirectional"))
    )
    (net (code "29") (name "Net-(U1-R_EXT)") (class "Default")
      (node (ref "R2") (pin "1") (pinfunction "1_1") (pintype "passive"))
      (node (ref "U1") (pin "6") (pinfunction "R_EXT_6") (pintype "bidirectional"))
    )
    (net (code "30") (name "VCC") (class "Default")
      (node (ref "C2") (pin "1") (pinfunction "1_1") (pintype "passive"))
      (node (ref "C3") (pin "1") (pinfunction "1_1") (pintype "passive"))
      (node (ref "C7") (pin "1") (pinfunction "1_1") (pintype "passive"))
      (node (ref "U1") (pin "2") (pinfunction "VCC_2") (pintype "power_in"))
    )
    (net (code "31") (name "unconnected-(U1-AUDIOIN-Pad17)") (class "Default")
      (node (ref "U1") (pin "17") (pinfunction "AUDIOIN_17") (pintype "input"))
    )
    (net (code "32") (name "unconnected-(U1-CB9-Pad15)") (class "Default")
      (node (ref "U1") (pin "15") (pinfunction "CB9_15") (pintype "bidirectional"))
    )
    (net (code "33") (name "unconnected-(U1-C_FILT-Pad16)") (class "Default")
      (node (ref "U1") (pin "16") (pinfunction "C_FILT_16") (pintype "bidirectional"))
    )
    (net (code "34") (name "unconnected-(U1-INTB-Pad4)") (class "Default")
      (node (ref "U1") (pin "4") (pinfunction "INTB_4") (pintype "output"))
    )
  )
)
